# ColourWatch.net
KiCad netlist of a schematic drawn in EAGLE
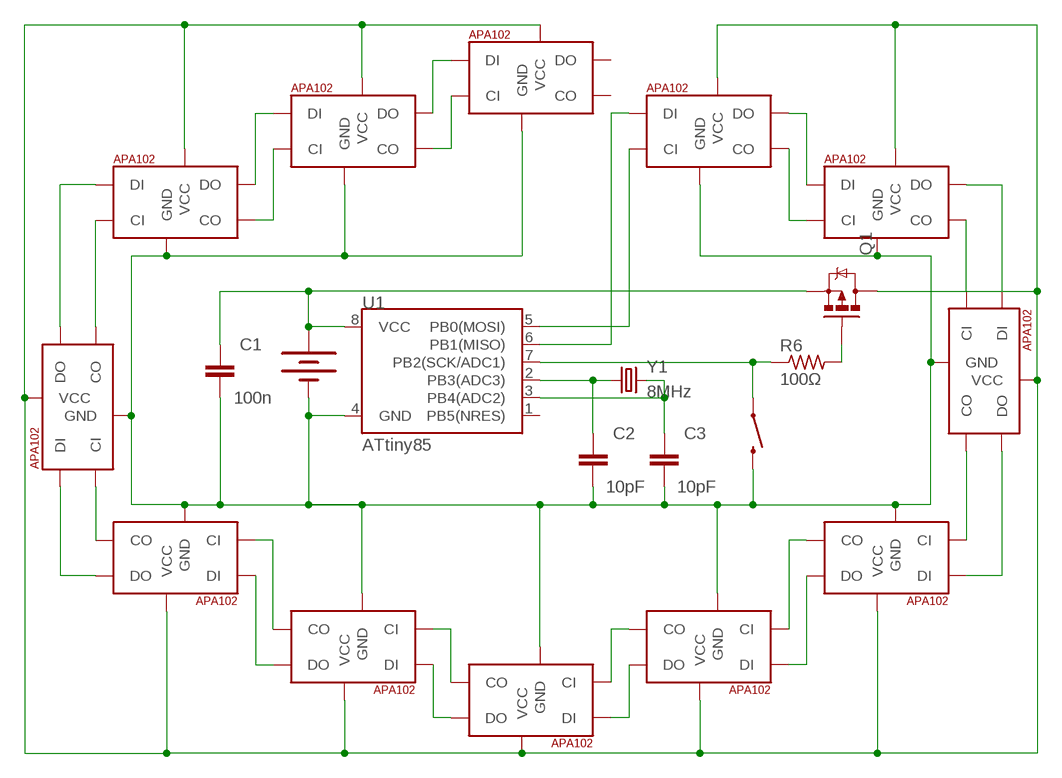
[diagram p0: schematic, sheet 1]

(export (version "E")
  (design (tool "Eeschema 10.0.6"))
  (components
    (comp (ref "1")
      (value "APA1022020")
      (footprint "eagle-import:APA102_2020")
      (libsource (lib "eagle-import") (part "APA1022020"))
    )
    (comp (ref "2")
      (value "APA1022020")
      (footprint "eagle-import:APA102_2020")
      (libsource (lib "eagle-import") (part "APA1022020"))
    )
    (comp (ref "3")
      (value "APA1022020")
      (footprint "eagle-import:APA102_2020")
      (libsource (lib "eagle-import") (part "APA1022020"))
    )
    (comp (ref "4")
      (value "APA1022020")
      (footprint "eagle-import:APA102_2020")
      (libsource (lib "eagle-import") (part "APA1022020"))
    )
    (comp (ref "5")
      (value "APA1022020")
      (footprint "eagle-import:APA102_2020")
      (libsource (lib "eagle-import") (part "APA1022020"))
    )
    (comp (ref "6")
      (value "APA1022020")
      (footprint "eagle-import:APA102_2020")
      (libsource (lib "eagle-import") (part "APA1022020"))
    )
    (comp (ref "7")
      (value "APA1022020")
      (footprint "eagle-import:APA102_2020")
      (libsource (lib "eagle-import") (part "APA1022020"))
    )
    (comp (ref "8")
      (value "APA1022020")
      (footprint "eagle-import:APA102_2020")
      (libsource (lib "eagle-import") (part "APA1022020"))
    )
    (comp (ref "9")
      (value "APA1022020")
      (footprint "eagle-import:APA102_2020")
      (libsource (lib "eagle-import") (part "APA1022020"))
    )
    (comp (ref "10")
      (value "APA1022020")
      (footprint "eagle-import:APA102_2020")
      (libsource (lib "eagle-import") (part "APA1022020"))
    )
    (comp (ref "11")
      (value "APA1022020")
      (footprint "eagle-import:APA102_2020")
      (libsource (lib "eagle-import") (part "APA1022020"))
    )
    (comp (ref "12")
      (value "APA1022020")
      (footprint "eagle-import:APA102_2020")
      (libsource (lib "eagle-import") (part "APA1022020"))
    )
    (comp (ref "BAT1")
      (value "20mm coincell")
      (footprint "eagle-import:BATTCON_20MM_4LEGS")
      (libsource (lib "eagle-import") (part "BATTERY20MM_4LEGS"))
    )
    (comp (ref "C1")
      (value "100n")
      (footprint "eagle-import:0603-CAP")
      (libsource (lib "eagle-import") (part "CAP0603-CAP"))
    )
    (comp (ref "C2")
      (value "10pF")
      (footprint "eagle-import:0603-CAP")
      (libsource (lib "eagle-import") (part "CAP0603-CAP"))
    )
    (comp (ref "C3")
      (value "10pF")
      (footprint "eagle-import:0603-CAP")
      (libsource (lib "eagle-import") (part "CAP0603-CAP"))
    )
    (comp (ref "Q1")
      (value "MOSFET-PCHANNELSMD")
      (footprint "eagle-import:SOT23-3")
      (libsource (lib "eagle-import") (part "MOSFET-PCHANNELSMD"))
    )
    (comp (ref "R6")
      (value "100Ω")
      (footprint "eagle-import:M0805")
      (libsource (lib "eagle-import") (part "R-US_M0805"))
    )
    (comp (ref "S2")
      (value "SWITCH-MOMENTARY-2SMD")
      (footprint "eagle-import:TACTILE-SWITCH-SMD")
      (libsource (lib "eagle-import") (part "SWITCH-MOMENTARY-2SMD"))
    )
    (comp (ref "U1")
      (value "ATtiny85")
      (footprint "eagle-import:SO08-EIAJ")
      (libsource (lib "eagle-import") (part "ATTINY45TINY45-20-SMT"))
    )
    (comp (ref "Y1")
      (value "8MHz")
      (footprint "eagle-import:CRYSTAL-SMD-5X3")
      (libsource (lib "eagle-import") (part "CRYSTALCRYSTAL-SMD-5X3-16MHZ"))
    )
  )
  (nets
    (net (code "1") (name "Net-(1-CI)") (class "Default")
      (node (ref "1") (pin "C_IN") (pinfunction "CI_C_IN") (pintype "bidirectional"))
      (node (ref "U1") (pin "5") (pinfunction "PB0(MOSI)_5") (pintype "bidirectional"))
    )
    (net (code "2") (name "Net-(1-CO)") (class "Default")
      (node (ref "1") (pin "CL_OUT") (pinfunction "CO_CL_OUT") (pintype "bidirectional"))
      (node (ref "2") (pin "C_IN") (pinfunction "CI_C_IN") (pintype "bidirectional"))
    )
    (net (code "3") (name "Net-(1-DI)") (class "Default")
      (node (ref "1") (pin "D_IN") (pinfunction "DI_D_IN") (pintype "bidirectional"))
      (node (ref "U1") (pin "6") (pinfunction "PB1(MISO)_6") (pintype "bidirectional"))
    )
    (net (code "4") (name "Net-(1-DO)") (class "Default")
      (node (ref "1") (pin "D_OUT") (pinfunction "DO_D_OUT") (pintype "bidirectional"))
      (node (ref "2") (pin "D_IN") (pinfunction "DI_D_IN") (pintype "bidirectional"))
    )
    (net (code "5") (name "Net-(1-VCC)") (class "Default")
      (node (ref "1") (pin "V_CC") (pinfunction "VCC_V_CC") (pintype "bidirectional"))
      (node (ref "10") (pin "V_CC") (pinfunction "VCC_V_CC") (pintype "bidirectional"))
      (node (ref "11") (pin "V_CC") (pinfunction "VCC_V_CC") (pintype "bidirectional"))
      (node (ref "12") (pin "V_CC") (pinfunction "VCC_V_CC") (pintype "bidirectional"))
      (node (ref "2") (pin "V_CC") (pinfunction "VCC_V_CC") (pintype "bidirectional"))
      (node (ref "3") (pin "V_CC") (pinfunction "VCC_V_CC") (pintype "bidirectional"))
      (node (ref "4") (pin "V_CC") (pinfunction "VCC_V_CC") (pintype "bidirectional"))
      (node (ref "5") (pin "V_CC") (pinfunction "VCC_V_CC") (pintype "bidirectional"))
      (node (ref "6") (pin "V_CC") (pinfunction "VCC_V_CC") (pintype "bidirectional"))
      (node (ref "7") (pin "V_CC") (pinfunction "VCC_V_CC") (pintype "bidirectional"))
      (node (ref "8") (pin "V_CC") (pinfunction "VCC_V_CC") (pintype "bidirectional"))
      (node (ref "9") (pin "V_CC") (pinfunction "VCC_V_CC") (pintype "bidirectional"))
      (node (ref "Q1") (pin "3") (pinfunction "D_3") (pintype "passive"))
    )
    (net (code "6") (name "Net-(2-CO)") (class "Default")
      (node (ref "2") (pin "CL_OUT") (pinfunction "CO_CL_OUT") (pintype "bidirectional"))
      (node (ref "3") (pin "C_IN") (pinfunction "CI_C_IN") (pintype "bidirectional"))
    )
    (net (code "7") (name "Net-(2-DO)") (class "Default")
      (node (ref "2") (pin "D_OUT") (pinfunction "DO_D_OUT") (pintype "bidirectional"))
      (node (ref "3") (pin "D_IN") (pinfunction "DI_D_IN") (pintype "bidirectional"))
    )
    (net (code "8") (name "Net-(3-CO)") (class "Default")
      (node (ref "3") (pin "CL_OUT") (pinfunction "CO_CL_OUT") (pintype "bidirectional"))
      (node (ref "4") (pin "C_IN") (pinfunction "CI_C_IN") (pintype "bidirectional"))
    )
    (net (code "9") (name "Net-(3-DO)") (class "Default")
      (node (ref "3") (pin "D_OUT") (pinfunction "DO_D_OUT") (pintype "bidirectional"))
      (node (ref "4") (pin "D_IN") (pinfunction "DI_D_IN") (pintype "bidirectional"))
    )
    (net (code "10") (name "Net-(4-CO)") (class "Default")
      (node (ref "4") (pin "CL_OUT") (pinfunction "CO_CL_OUT") (pintype "bidirectional"))
      (node (ref "5") (pin "C_IN") (pinfunction "CI_C_IN") (pintype "bidirectional"))
    )
    (net (code "11") (name "Net-(4-DO)") (class "Default")
      (node (ref "4") (pin "D_OUT") (pinfunction "DO_D_OUT") (pintype "bidirectional"))
      (node (ref "5") (pin "D_IN") (pinfunction "DI_D_IN") (pintype "bidirectional"))
    )
    (net (code "12") (name "Net-(5-CO)") (class "Default")
      (node (ref "5") (pin "CL_OUT") (pinfunction "CO_CL_OUT") (pintype "bidirectional"))
      (node (ref "6") (pin "C_IN") (pinfunction "CI_C_IN") (pintype "bidirectional"))
    )
    (net (code "13") (name "Net-(5-DO)") (class "Default")
      (node (ref "5") (pin "D_OUT") (pinfunction "DO_D_OUT") (pintype "bidirectional"))
      (node (ref "6") (pin "D_IN") (pinfunction "DI_D_IN") (pintype "bidirectional"))
    )
    (net (code "14") (name "Net-(6-CO)") (class "Default")
      (node (ref "6") (pin "CL_OUT") (pinfunction "CO_CL_OUT") (pintype "bidirectional"))
      (node (ref "7") (pin "C_IN") (pinfunction "CI_C_IN") (pintype "bidirectional"))
    )
    (net (code "15") (name "Net-(6-DO)") (class "Default")
      (node (ref "6") (pin "D_OUT") (pinfunction "DO_D_OUT") (pintype "bidirectional"))
      (node (ref "7") (pin "D_IN") (pinfunction "DI_D_IN") (pintype "bidirectional"))
    )
    (net (code "16") (name "Net-(7-CO)") (class "Default")
      (node (ref "7") (pin "CL_OUT") (pinfunction "CO_CL_OUT") (pintype "bidirectional"))
      (node (ref "8") (pin "C_IN") (pinfunction "CI_C_IN") (pintype "bidirectional"))
    )
    (net (code "17") (name "Net-(7-DO)") (class "Default")
      (node (ref "7") (pin "D_OUT") (pinfunction "DO_D_OUT") (pintype "bidirectional"))
      (node (ref "8") (pin "D_IN") (pinfunction "DI_D_IN") (pintype "bidirectional"))
    )
    (net (code "18") (name "Net-(8-CO)") (class "Default")
      (node (ref "8") (pin "CL_OUT") (pinfunction "CO_CL_OUT") (pintype "bidirectional"))
      (node (ref "9") (pin "C_IN") (pinfunction "CI_C_IN") (pintype "bidirectional"))
    )
    (net (code "19") (name "Net-(8-DO)") (class "Default")
      (node (ref "8") (pin "D_OUT") (pinfunction "DO_D_OUT") (pintype "bidirectional"))
      (node (ref "9") (pin "D_IN") (pinfunction "DI_D_IN") (pintype "bidirectional"))
    )
    (net (code "20") (name "Net-(10-CI)") (class "Default")
      (node (ref "10") (pin "C_IN") (pinfunction "CI_C_IN") (pintype "bidirectional"))
      (node (ref "9") (pin "CL_OUT") (pinfunction "CO_CL_OUT") (pintype "bidirectional"))
    )
    (net (code "21") (name "Net-(10-CO)") (class "Default")
      (node (ref "10") (pin "CL_OUT") (pinfunction "CO_CL_OUT") (pintype "bidirectional"))
      (node (ref "11") (pin "C_IN") (pinfunction "CI_C_IN") (pintype "bidirectional"))
    )
    (net (code "22") (name "Net-(10-DI)") (class "Default")
      (node (ref "10") (pin "D_IN") (pinfunction "DI_D_IN") (pintype "bidirectional"))
      (node (ref "9") (pin "D_OUT") (pinfunction "DO_D_OUT") (pintype "bidirectional"))
    )
    (net (code "23") (name "Net-(10-DO)") (class "Default")
      (node (ref "10") (pin "D_OUT") (pinfunction "DO_D_OUT") (pintype "bidirectional"))
      (node (ref "11") (pin "D_IN") (pinfunction "DI_D_IN") (pintype "bidirectional"))
    )
    (net (code "24") (name "Net-(11-CO)") (class "Default")
      (node (ref "11") (pin "CL_OUT") (pinfunction "CO_CL_OUT") (pintype "bidirectional"))
      (node (ref "12") (pin "C_IN") (pinfunction "CI_C_IN") (pintype "bidirectional"))
    )
    (net (code "25") (name "Net-(11-DO)") (class "Default")
      (node (ref "11") (pin "D_OUT") (pinfunction "DO_D_OUT") (pintype "bidirectional"))
      (node (ref "12") (pin "D_IN") (pinfunction "DI_D_IN") (pintype "bidirectional"))
    )
    (net (code "26") (name "Net-(BAT1--)") (class "Default")
      (node (ref "1") (pin "GND") (pinfunction "GND_GND") (pintype "bidirectional"))
      (node (ref "10") (pin "GND") (pinfunction "GND_GND") (pintype "bidirectional"))
      (node (ref "11") (pin "GND") (pinfunction "GND_GND") (pintype "bidirectional"))
      (node (ref "12") (pin "GND") (pinfunction "GND_GND") (pintype "bidirectional"))
      (node (ref "2") (pin "GND") (pinfunction "GND_GND") (pintype "bidirectional"))
      (node (ref "3") (pin "GND") (pinfunction "GND_GND") (pintype "bidirectional"))
      (node (ref "4") (pin "GND") (pinfunction "GND_GND") (pintype "bidirectional"))
      (node (ref "5") (pin "GND") (pinfunction "GND_GND") (pintype "bidirectional"))
      (node (ref "6") (pin "GND") (pinfunction "GND_GND") (pintype "bidirectional"))
      (node (ref "7") (pin "GND") (pinfunction "GND_GND") (pintype "bidirectional"))
      (node (ref "8") (pin "GND") (pinfunction "GND_GND") (pintype "bidirectional"))
      (node (ref "9") (pin "GND") (pinfunction "GND_GND") (pintype "bidirectional"))
      (node (ref "BAT1") (pin "NEGATIVE") (pinfunction "-_NEGATIVE") (pintype "power_in"))
      (node (ref "C1") (pin "2") (pinfunction "2_2") (pintype "passive"))
      (node (ref "C2") (pin "2") (pinfunction "2_2") (pintype "passive"))
      (node (ref "C3") (pin "2") (pinfunction "2_2") (pintype "passive"))
      (node (ref "S2") (pin "3") (pinfunction "2_3") (pintype "passive"))
      (node (ref "U1") (pin "4") (pinfunction "GND_4") (pintype "bidirectional"))
    )
    (net (code "27") (name "Net-(Q1-G)") (class "Default")
      (node (ref "Q1") (pin "1") (pinfunction "G_1") (pintype "passive"))
      (node (ref "R6") (pin "2") (pinfunction "2_2") (pintype "passive"))
    )
    (net (code "28") (name "Net-(Q1-S)") (class "Default")
      (node (ref "BAT1") (pin "POSITIVE@1") (pinfunction "+_POSITIVE@1") (pintype "power_in"))
      (node (ref "BAT1") (pin "POSITIVE@2") (pinfunction "+_POSITIVE@2") (pintype "power_in"))
      (node (ref "BAT1") (pin "POSITIVE@3") (pinfunction "+_POSITIVE@3") (pintype "power_in"))
      (node (ref "BAT1") (pin "POSITIVE@4") (pinfunction "+_POSITIVE@4") (pintype "power_in"))
      (node (ref "C1") (pin "1") (pinfunction "1_1") (pintype "passive"))
      (node (ref "Q1") (pin "2") (pinfunction "S_2") (pintype "passive"))
      (node (ref "U1") (pin "8") (pinfunction "VCC_8") (pintype "bidirectional"))
    )
    (net (code "29") (name "Net-(U1-PB2(SCK{slash}ADC1))") (class "Default")
      (node (ref "R6") (pin "1") (pinfunction "1_1") (pintype "passive"))
      (node (ref "S2") (pin "1") (pinfunction "1_1") (pintype "passive"))
      (node (ref "U1") (pin "7") (pinfunction "PB2(SCK/ADC1)_7") (pintype "bidirectional"))
    )
    (net (code "30") (name "Net-(U1-PB3(ADC3))") (class "Default")
      (node (ref "C2") (pin "1") (pinfunction "1_1") (pintype "passive"))
      (node (ref "U1") (pin "2") (pinfunction "PB3(ADC3)_2") (pintype "bidirectional"))
      (node (ref "Y1") (pin "1") (pinfunction "1_1") (pintype "passive"))
    )
    (net (code "31") (name "Net-(U1-PB4(ADC2))") (class "Default")
      (node (ref "C3") (pin "1") (pinfunction "1_1") (pintype "passive"))
      (node (ref "U1") (pin "3") (pinfunction "PB4(ADC2)_3") (pintype "bidirectional"))
      (node (ref "Y1") (pin "3") (pinfunction "2_3") (pintype "passive"))
    )
    (net (code "32") (name "unconnected-(12-CO-PadCL_OUT)") (class "Default")
      (node (ref "12") (pin "CL_OUT") (pinfunction "CO_CL_OUT") (pintype "bidirectional"))
    )
    (net (code "33") (name "unconnected-(12-DO-PadD_OUT)") (class "Default")
      (node (ref "12") (pin "D_OUT") (pinfunction "DO_D_OUT") (pintype "bidirectional"))
    )
    (net (code "34") (name "unconnected-(U1-PB5(NRES)-Pad1)") (class "Default")
      (node (ref "U1") (pin "1") (pinfunction "PB5(NRES)_1") (pintype "bidirectional"))
    )
  )
)
